# drivers.net
KiCad netlist of a schematic drawn in Altium Designer
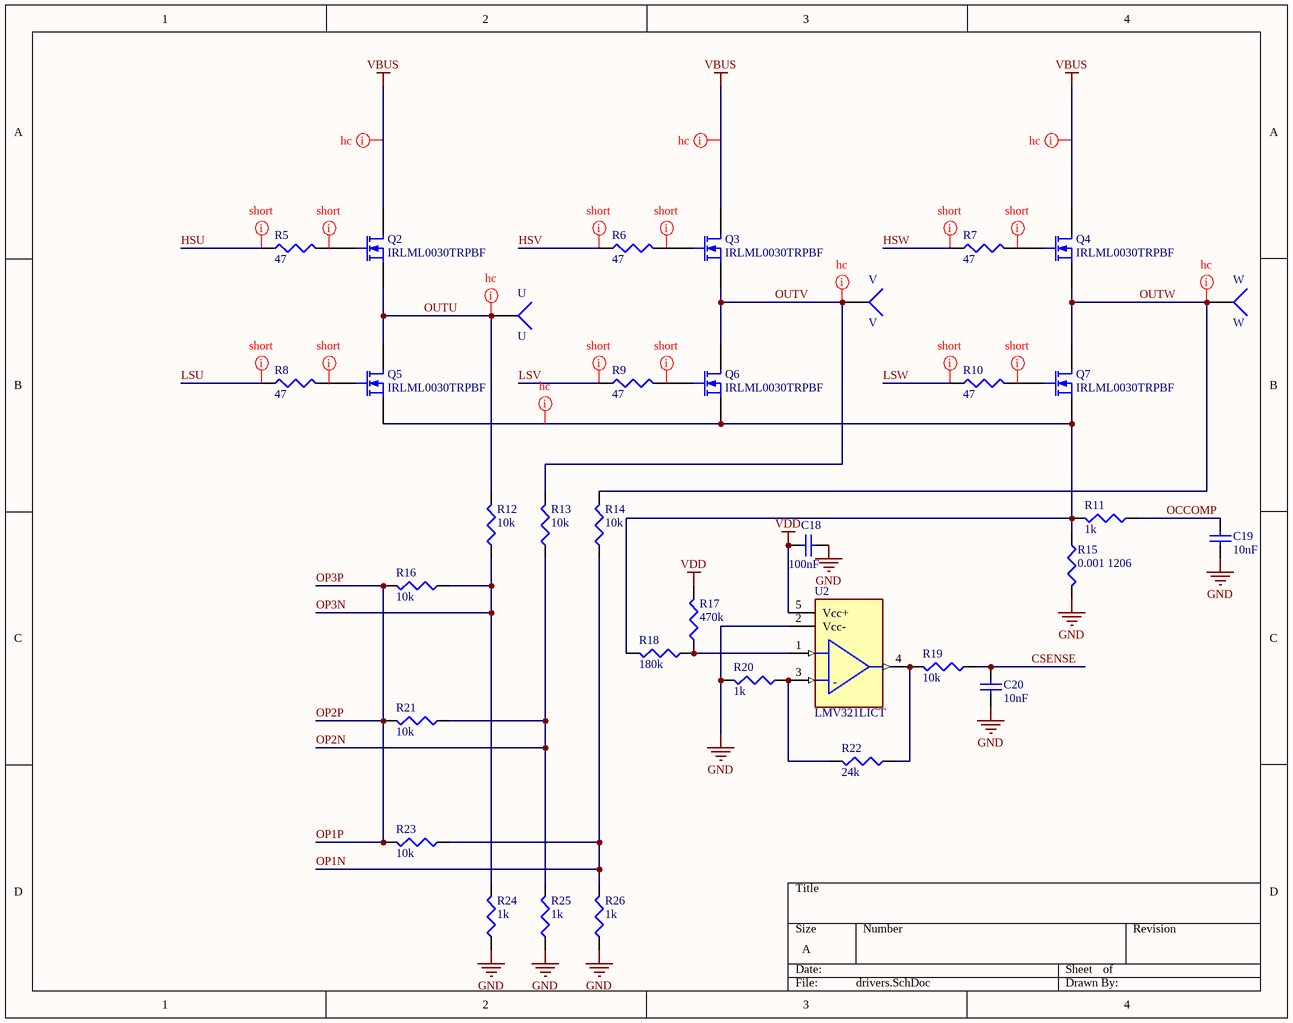
[diagram p0: drivers.SchDoc]

(export (version "E")
  (design (tool "Eeschema 10.0.6"))
  (components
    (comp (ref "C18")
      (value "100nF")
      (description "Capacitor")
      (fields (field (name "PUBLISHER") "Altium Limited"))
      (libsource (lib "Miscellaneous Devices") (part "Cap"))
    )
    (comp (ref "C19")
      (value "10nF")
      (description "Capacitor")
      (fields (field (name "PUBLISHER") "Altium Limited"))
      (libsource (lib "Miscellaneous Devices") (part "Cap"))
    )
    (comp (ref "C20")
      (value "10nF")
      (description "Capacitor")
      (fields (field (name "PUBLISHER") "Altium Limited"))
      (libsource (lib "Miscellaneous Devices") (part "Cap"))
    )
    (comp (ref "Q2")
      (value "IRLML0030TRPBF")
      (footprint "Micro3")
      (description "N-Channel MOSFET")
      (fields (field (name "PUBLISHER") "Altium Limited"))
      (libsource (lib "Miscellaneous Devices") (part "MOSFET-N"))
    )
    (comp (ref "Q3")
      (value "IRLML0030TRPBF")
      (footprint "Micro3")
      (description "N-Channel MOSFET")
      (fields (field (name "PUBLISHER") "Altium Limited"))
      (libsource (lib "Miscellaneous Devices") (part "MOSFET-N"))
    )
    (comp (ref "Q4")
      (value "IRLML0030TRPBF")
      (footprint "Micro3")
      (description "N-Channel MOSFET")
      (fields (field (name "PUBLISHER") "Altium Limited"))
      (libsource (lib "Miscellaneous Devices") (part "MOSFET-N"))
    )
    (comp (ref "Q5")
      (value "IRLML0030TRPBF")
      (footprint "Micro3")
      (description "N-Channel MOSFET")
      (fields (field (name "PUBLISHER") "Altium Limited"))
      (libsource (lib "Miscellaneous Devices") (part "MOSFET-N"))
    )
    (comp (ref "Q6")
      (value "IRLML0030TRPBF")
      (footprint "Micro3")
      (description "N-Channel MOSFET")
      (fields (field (name "PUBLISHER") "Altium Limited"))
      (libsource (lib "Miscellaneous Devices") (part "MOSFET-N"))
    )
    (comp (ref "Q7")
      (value "IRLML0030TRPBF")
      (footprint "Micro3")
      (description "N-Channel MOSFET")
      (fields (field (name "PUBLISHER") "Altium Limited"))
      (libsource (lib "Miscellaneous Devices") (part "MOSFET-N"))
    )
    (comp (ref "R5")
      (value "47")
      (description "Resistor")
      (fields (field (name "PUBLISHER") "Altium Limited"))
      (libsource (lib "Miscellaneous Devices") (part "Res3"))
    )
    (comp (ref "R6")
      (value "47")
      (description "Resistor")
      (fields (field (name "PUBLISHER") "Altium Limited"))
      (libsource (lib "Miscellaneous Devices") (part "Res3"))
    )
    (comp (ref "R7")
      (value "47")
      (description "Resistor")
      (fields (field (name "PUBLISHER") "Altium Limited"))
      (libsource (lib "Miscellaneous Devices") (part "Res3"))
    )
    (comp (ref "R8")
      (value "47")
      (description "Resistor")
      (fields (field (name "PUBLISHER") "Altium Limited"))
      (libsource (lib "Miscellaneous Devices") (part "Res3"))
    )
    (comp (ref "R9")
      (value "47")
      (description "Resistor")
      (fields (field (name "PUBLISHER") "Altium Limited"))
      (libsource (lib "Miscellaneous Devices") (part "Res3"))
    )
    (comp (ref "R10")
      (value "47")
      (description "Resistor")
      (fields (field (name "PUBLISHER") "Altium Limited"))
      (libsource (lib "Miscellaneous Devices") (part "Res3"))
    )
    (comp (ref "R11")
      (value "1k")
      (description "Resistor")
      (fields (field (name "PUBLISHER") "Altium Limited"))
      (libsource (lib "Miscellaneous Devices") (part "Res3"))
    )
    (comp (ref "R12")
      (value "10k")
      (description "Resistor")
      (fields (field (name "PUBLISHER") "Altium Limited"))
      (libsource (lib "Miscellaneous Devices") (part "Res3"))
    )
    (comp (ref "R13")
      (value "10k")
      (description "Resistor")
      (fields (field (name "PUBLISHER") "Altium Limited"))
      (libsource (lib "Miscellaneous Devices") (part "Res3"))
    )
    (comp (ref "R14")
      (value "10k")
      (description "Resistor")
      (fields (field (name "PUBLISHER") "Altium Limited"))
      (libsource (lib "Miscellaneous Devices") (part "Res3"))
    )
    (comp (ref "R15")
      (value "0.001 1206")
      (footprint "MY_1206")
      (description "Resistor")
      (fields (field (name "PUBLISHER") "Altium Limited"))
      (libsource (lib "Miscellaneous Devices") (part "Res3"))
    )
    (comp (ref "R16")
      (value "10k")
      (description "Resistor")
      (fields (field (name "PUBLISHER") "Altium Limited"))
      (libsource (lib "Miscellaneous Devices") (part "Res3"))
    )
    (comp (ref "R17")
      (value "470k")
      (description "Resistor")
      (fields (field (name "PUBLISHER") "Altium Limited"))
      (libsource (lib "Miscellaneous Devices") (part "Res3"))
    )
    (comp (ref "R18")
      (value "180k")
      (description "Resistor")
      (fields (field (name "PUBLISHER") "Altium Limited"))
      (libsource (lib "Miscellaneous Devices") (part "Res3"))
    )
    (comp (ref "R19")
      (value "10k")
      (description "Resistor")
      (fields (field (name "PUBLISHER") "Altium Limited"))
      (libsource (lib "Miscellaneous Devices") (part "Res3"))
    )
    (comp (ref "R20")
      (value "1k")
      (description "Resistor")
      (fields (field (name "PUBLISHER") "Altium Limited"))
      (libsource (lib "Miscellaneous Devices") (part "Res3"))
    )
    (comp (ref "R21")
      (value "10k")
      (description "Resistor")
      (fields (field (name "PUBLISHER") "Altium Limited"))
      (libsource (lib "Miscellaneous Devices") (part "Res3"))
    )
    (comp (ref "R22")
      (value "24k")
      (description "Resistor")
      (fields (field (name "PUBLISHER") "Altium Limited"))
      (libsource (lib "Miscellaneous Devices") (part "Res3"))
    )
    (comp (ref "R23")
      (value "10k")
      (description "Resistor")
      (fields (field (name "PUBLISHER") "Altium Limited"))
      (libsource (lib "Miscellaneous Devices") (part "Res3"))
    )
    (comp (ref "R24")
      (value "1k")
      (description "Resistor")
      (fields (field (name "PUBLISHER") "Altium Limited"))
      (libsource (lib "Miscellaneous Devices") (part "Res3"))
    )
    (comp (ref "R25")
      (value "1k")
      (description "Resistor")
      (fields (field (name "PUBLISHER") "Altium Limited"))
      (libsource (lib "Miscellaneous Devices") (part "Res3"))
    )
    (comp (ref "R26")
      (value "1k")
      (description "Resistor")
      (fields (field (name "PUBLISHER") "Altium Limited"))
      (libsource (lib "Miscellaneous Devices") (part "Res3"))
    )
    (comp (ref "U")
      (value "U")
      (footprint "solder_pin_small")
      (description "Socket")
      (fields (field (name "PUBLISHER") "Altium Limited"))
      (libsource (lib "Miscellaneous Connectors") (part "Socket"))
    )
    (comp (ref "U2")
      (value "LMV321LICT")
      (footprint "FP-SOT323-5-IPC_C")
      (description "IC OPAMP GP 1 CIRCUIT SC70-5")
      (fields
        (field (name "MANUFACTURER") "STMicroelectronics")
        (field (name "OCTOPART") "https://octopart.com/lmv321lict-stmicroelectronics-23014003")
      )
      (libsource (lib "Altium Content Vault") (part "c0016de229fc905e56f16c40abb9bc5"))
    )
    (comp (ref "V")
      (value "V")
      (footprint "solder_pin_small")
      (description "Socket")
      (fields (field (name "PUBLISHER") "Altium Limited"))
      (libsource (lib "Miscellaneous Connectors") (part "Socket"))
    )
    (comp (ref "W")
      (value "W")
      (footprint "solder_pin_small")
      (description "Socket")
      (fields (field (name "PUBLISHER") "Altium Limited"))
      (libsource (lib "Miscellaneous Connectors") (part "Socket"))
    )
  )
  (nets
    (net (code "1") (name "/CSENSE") (class "Default")
      (node (ref "C20") (pin "2") (pinfunction "2_2") (pintype "passive"))
      (node (ref "R19") (pin "1") (pinfunction "1_1") (pintype "passive"))
    )
    (net (code "2") (name "/HSU") (class "Default")
      (node (ref "R5") (pin "1") (pinfunction "1_1") (pintype "passive"))
    )
    (net (code "3") (name "/HSV") (class "Default")
      (node (ref "R6") (pin "1") (pinfunction "1_1") (pintype "passive"))
    )
    (net (code "4") (name "/HSW") (class "Default")
      (node (ref "R7") (pin "1") (pinfunction "1_1") (pintype "passive"))
    )
    (net (code "5") (name "/LSU") (class "Default")
      (node (ref "R8") (pin "1") (pinfunction "1_1") (pintype "passive"))
    )
    (net (code "6") (name "/LSV") (class "Default")
      (node (ref "R9") (pin "1") (pinfunction "1_1") (pintype "passive"))
    )
    (net (code "7") (name "/LSW") (class "Default")
      (node (ref "R10") (pin "1") (pinfunction "1_1") (pintype "passive"))
    )
    (net (code "8") (name "/OCCOMP") (class "Default")
      (node (ref "C19") (pin "2") (pinfunction "2_2") (pintype "passive"))
      (node (ref "R11") (pin "1") (pinfunction "1_1") (pintype "passive"))
    )
    (net (code "9") (name "/OP1N") (class "Default")
      (node (ref "R14") (pin "1") (pinfunction "1_1") (pintype "passive"))
      (node (ref "R23") (pin "1") (pinfunction "1_1") (pintype "passive"))
      (node (ref "R26") (pin "2") (pinfunction "2_2") (pintype "passive"))
    )
    (net (code "10") (name "/OP1P") (class "Default")
      (node (ref "R16") (pin "2") (pinfunction "2_2") (pintype "passive"))
      (node (ref "R21") (pin "2") (pinfunction "2_2") (pintype "passive"))
      (node (ref "R23") (pin "2") (pinfunction "2_2") (pintype "passive"))
    )
    (net (code "11") (name "/OP2N") (class "Default")
      (node (ref "R13") (pin "1") (pinfunction "1_1") (pintype "passive"))
      (node (ref "R21") (pin "1") (pinfunction "1_1") (pintype "passive"))
      (node (ref "R25") (pin "2") (pinfunction "2_2") (pintype "passive"))
    )
    (net (code "12") (name "/OP3N") (class "Default")
      (node (ref "R12") (pin "1") (pinfunction "1_1") (pintype "passive"))
      (node (ref "R16") (pin "1") (pinfunction "1_1") (pintype "passive"))
      (node (ref "R24") (pin "2") (pinfunction "2_2") (pintype "passive"))
    )
    (net (code "13") (name "/OUTU") (class "Default")
      (node (ref "Q2") (pin "S") (pinfunction "S_S") (pintype "passive"))
      (node (ref "Q5") (pin "D") (pinfunction "D_D") (pintype "passive"))
      (node (ref "R12") (pin "2") (pinfunction "2_2") (pintype "passive"))
      (node (ref "U") (pin "1") (pinfunction "1_1") (pintype "passive"))
    )
    (net (code "14") (name "/OUTV") (class "Default")
      (node (ref "Q3") (pin "S") (pinfunction "S_S") (pintype "passive"))
      (node (ref "Q6") (pin "D") (pinfunction "D_D") (pintype "passive"))
      (node (ref "R13") (pin "2") (pinfunction "2_2") (pintype "passive"))
      (node (ref "V") (pin "1") (pinfunction "1_1") (pintype "passive"))
    )
    (net (code "15") (name "/OUTW") (class "Default")
      (node (ref "Q4") (pin "S") (pinfunction "S_S") (pintype "passive"))
      (node (ref "Q7") (pin "D") (pinfunction "D_D") (pintype "passive"))
      (node (ref "R14") (pin "2") (pinfunction "2_2") (pintype "passive"))
      (node (ref "W") (pin "1") (pinfunction "1_1") (pintype "passive"))
    )
    (net (code "16") (name "GND") (class "Default")
      (node (ref "C18") (pin "2") (pinfunction "2_2") (pintype "passive"))
      (node (ref "C19") (pin "1") (pinfunction "1_1") (pintype "passive"))
      (node (ref "C20") (pin "1") (pinfunction "1_1") (pintype "passive"))
      (node (ref "R15") (pin "2") (pinfunction "2_2") (pintype "passive"))
      (node (ref "R20") (pin "2") (pinfunction "2_2") (pintype "passive"))
      (node (ref "R24") (pin "1") (pinfunction "1_1") (pintype "passive"))
      (node (ref "R25") (pin "1") (pinfunction "1_1") (pintype "passive"))
      (node (ref "R26") (pin "1") (pinfunction "1_1") (pintype "passive"))
      (node (ref "U2") (pin "2") (pinfunction "Vcc-_2") (pintype "power_in"))
    )
    (net (code "17") (name "Net-(Q2-PadG)") (class "Default")
      (node (ref "Q2") (pin "G") (pinfunction "G_G") (pintype "passive"))
      (node (ref "R5") (pin "2") (pinfunction "2_2") (pintype "passive"))
    )
    (net (code "18") (name "Net-(Q3-PadG)") (class "Default")
      (node (ref "Q3") (pin "G") (pinfunction "G_G") (pintype "passive"))
      (node (ref "R6") (pin "2") (pinfunction "2_2") (pintype "passive"))
    )
    (net (code "19") (name "Net-(Q4-PadG)") (class "Default")
      (node (ref "Q4") (pin "G") (pinfunction "G_G") (pintype "passive"))
      (node (ref "R7") (pin "2") (pinfunction "2_2") (pintype "passive"))
    )
    (net (code "20") (name "Net-(Q5-PadG)") (class "Default")
      (node (ref "Q5") (pin "G") (pinfunction "G_G") (pintype "passive"))
      (node (ref "R8") (pin "2") (pinfunction "2_2") (pintype "passive"))
    )
    (net (code "21") (name "Net-(Q5-PadS)") (class "Default")
      (node (ref "Q5") (pin "S") (pinfunction "S_S") (pintype "passive"))
      (node (ref "Q6") (pin "S") (pinfunction "S_S") (pintype "passive"))
      (node (ref "Q7") (pin "S") (pinfunction "S_S") (pintype "passive"))
      (node (ref "R11") (pin "2") (pinfunction "2_2") (pintype "passive"))
      (node (ref "R15") (pin "1") (pinfunction "1_1") (pintype "passive"))
      (node (ref "R18") (pin "2") (pinfunction "2_2") (pintype "passive"))
    )
    (net (code "22") (name "Net-(Q6-PadG)") (class "Default")
      (node (ref "Q6") (pin "G") (pinfunction "G_G") (pintype "passive"))
      (node (ref "R9") (pin "2") (pinfunction "2_2") (pintype "passive"))
    )
    (net (code "23") (name "Net-(Q7-PadG)") (class "Default")
      (node (ref "Q7") (pin "G") (pinfunction "G_G") (pintype "passive"))
      (node (ref "R10") (pin "2") (pinfunction "2_2") (pintype "passive"))
    )
    (net (code "24") (name "Net-(U2-In+)") (class "Default")
      (node (ref "R17") (pin "1") (pinfunction "1_1") (pintype "passive"))
      (node (ref "R18") (pin "1") (pinfunction "1_1") (pintype "passive"))
      (node (ref "U2") (pin "1") (pinfunction "In+_1") (pintype "input"))
    )
    (net (code "25") (name "Net-(U2-In-)") (class "Default")
      (node (ref "R20") (pin "1") (pinfunction "1_1") (pintype "passive"))
      (node (ref "R22") (pin "2") (pinfunction "2_2") (pintype "passive"))
      (node (ref "U2") (pin "3") (pinfunction "In-_3") (pintype "input"))
    )
    (net (code "26") (name "Net-(U2-Out)") (class "Default")
      (node (ref "R19") (pin "2") (pinfunction "2_2") (pintype "passive"))
      (node (ref "R22") (pin "1") (pinfunction "1_1") (pintype "passive"))
      (node (ref "U2") (pin "4") (pinfunction "Out_4") (pintype "output"))
    )
    (net (code "27") (name "VBUS") (class "Default")
      (node (ref "Q2") (pin "D") (pinfunction "D_D") (pintype "passive"))
      (node (ref "Q3") (pin "D") (pinfunction "D_D") (pintype "passive"))
      (node (ref "Q4") (pin "D") (pinfunction "D_D") (pintype "passive"))
    )
    (net (code "28") (name "VDD") (class "Default")
      (node (ref "C18") (pin "1") (pinfunction "1_1") (pintype "passive"))
      (node (ref "R17") (pin "2") (pinfunction "2_2") (pintype "passive"))
      (node (ref "U2") (pin "5") (pinfunction "Vcc+_5") (pintype "power_in"))
    )
  )
)
